# plaque2.net
KiCad netlist of a schematic drawn in EAGLE
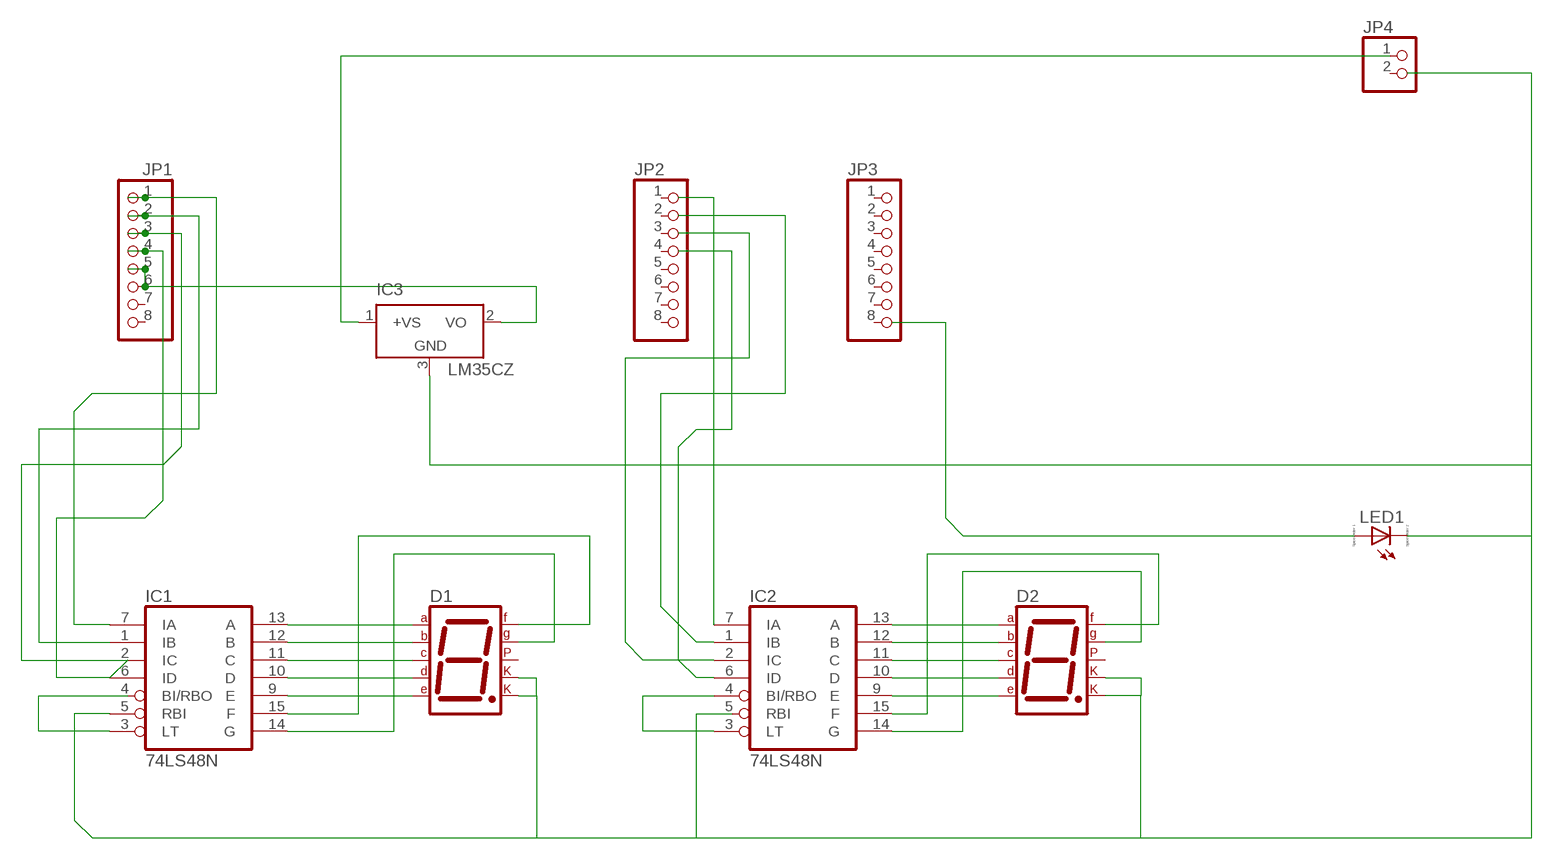
[diagram p0: schematic, sheet 1]

(export (version "E")
  (design (tool "Eeschema 10.0.6"))
  (components
    (comp (ref "D1")
      (value "7SEG-CK")
      (footprint "eagle-import:7SEG-13")
      (libsource (lib "eagle-import") (part "7SEG-CK"))
    )
    (comp (ref "D2")
      (value "7SEG-CK")
      (footprint "eagle-import:7SEG-13")
      (libsource (lib "eagle-import") (part "7SEG-CK"))
    )
    (comp (ref "IC1")
      (value "74LS48N")
      (footprint "eagle-import:DIL16")
      (libsource (lib "eagle-import") (part "7448NLS"))
    )
    (comp (ref "IC2")
      (value "74LS48N")
      (footprint "eagle-import:DIL16")
      (libsource (lib "eagle-import") (part "7448NLS"))
    )
    (comp (ref "IC3")
      (value "LM35CZ")
      (footprint "eagle-import:TO92")
      (libsource (lib "eagle-import") (part "LM35CZ"))
    )
    (comp (ref "JP1")
      (value "PINHD-1X8")
      (footprint "eagle-import:1X08")
      (libsource (lib "eagle-import") (part "PINHD-1X8"))
    )
    (comp (ref "JP2")
      (value "PINHD-1X8")
      (footprint "eagle-import:1X08")
      (libsource (lib "eagle-import") (part "PINHD-1X8"))
    )
    (comp (ref "JP3")
      (value "PINHD-1X8")
      (footprint "eagle-import:1X08")
      (libsource (lib "eagle-import") (part "PINHD-1X8"))
    )
    (comp (ref "JP4")
      (value "PINHD-1X2")
      (footprint "eagle-import:1X02")
      (libsource (lib "eagle-import") (part "PINHD-1X2"))
    )
    (comp (ref "LED1")
      (value "LED_E")
      (footprint "eagle-import:LED_1206")
      (libsource (lib "eagle-import") (part "LED_E"))
    )
  )
  (nets
    (net (code "1") (name "Net-(D1-A)") (class "Default")
      (node (ref "D1") (pin "7") (pinfunction "A_7") (pintype "passive"))
      (node (ref "IC1") (pin "13") (pinfunction "A_13") (pintype "output"))
    )
    (net (code "2") (name "Net-(D1-B)") (class "Default")
      (node (ref "D1") (pin "6") (pinfunction "B_6") (pintype "passive"))
      (node (ref "IC1") (pin "12") (pinfunction "B_12") (pintype "output"))
    )
    (net (code "3") (name "Net-(D1-C)") (class "Default")
      (node (ref "D1") (pin "4") (pinfunction "C_4") (pintype "passive"))
      (node (ref "IC1") (pin "11") (pinfunction "C_11") (pintype "output"))
    )
    (net (code "4") (name "Net-(D1-CK1)") (class "Default")
      (node (ref "D1") (pin "3") (pinfunction "CK1_3") (pintype "passive"))
      (node (ref "D1") (pin "8") (pinfunction "CK2_8") (pintype "passive"))
      (node (ref "D2") (pin "3") (pinfunction "CK1_3") (pintype "passive"))
      (node (ref "D2") (pin "8") (pinfunction "CK2_8") (pintype "passive"))
      (node (ref "IC1") (pin "5") (pinfunction "RBI_5") (pintype "input"))
      (node (ref "IC3") (pin "3") (pinfunction "GND_3") (pintype "power_in"))
      (node (ref "LED1") (pin "C") (pinfunction "C_C") (pintype "passive"))
    )
    (net (code "5") (name "Net-(D1-D)") (class "Default")
      (node (ref "D1") (pin "2") (pinfunction "D_2") (pintype "passive"))
      (node (ref "IC1") (pin "10") (pinfunction "D_10") (pintype "output"))
    )
    (net (code "6") (name "Net-(D1-E)") (class "Default")
      (node (ref "D1") (pin "1") (pinfunction "E_1") (pintype "passive"))
      (node (ref "IC1") (pin "9") (pinfunction "E_9") (pintype "output"))
    )
    (net (code "7") (name "Net-(D1-F)") (class "Default")
      (node (ref "D1") (pin "9") (pinfunction "F_9") (pintype "passive"))
      (node (ref "IC1") (pin "15") (pinfunction "F_15") (pintype "output"))
    )
    (net (code "8") (name "Net-(D1-G)") (class "Default")
      (node (ref "D1") (pin "10") (pinfunction "G_10") (pintype "passive"))
      (node (ref "IC1") (pin "14") (pinfunction "G_14") (pintype "output"))
    )
    (net (code "9") (name "Net-(D2-A)") (class "Default")
      (node (ref "D2") (pin "7") (pinfunction "A_7") (pintype "passive"))
      (node (ref "IC2") (pin "13") (pinfunction "A_13") (pintype "output"))
    )
    (net (code "10") (name "Net-(D2-B)") (class "Default")
      (node (ref "D2") (pin "6") (pinfunction "B_6") (pintype "passive"))
      (node (ref "IC2") (pin "12") (pinfunction "B_12") (pintype "output"))
    )
    (net (code "11") (name "Net-(D2-C)") (class "Default")
      (node (ref "D2") (pin "4") (pinfunction "C_4") (pintype "passive"))
      (node (ref "IC2") (pin "11") (pinfunction "C_11") (pintype "output"))
    )
    (net (code "12") (name "Net-(D2-D)") (class "Default")
      (node (ref "D2") (pin "2") (pinfunction "D_2") (pintype "passive"))
      (node (ref "IC2") (pin "10") (pinfunction "D_10") (pintype "output"))
    )
    (net (code "13") (name "Net-(D2-E)") (class "Default")
      (node (ref "D2") (pin "1") (pinfunction "E_1") (pintype "passive"))
      (node (ref "IC2") (pin "9") (pinfunction "E_9") (pintype "output"))
    )
    (net (code "14") (name "Net-(D2-F)") (class "Default")
      (node (ref "D2") (pin "9") (pinfunction "F_9") (pintype "passive"))
      (node (ref "IC2") (pin "15") (pinfunction "F_15") (pintype "output"))
    )
    (net (code "15") (name "Net-(D2-G)") (class "Default")
      (node (ref "D2") (pin "10") (pinfunction "G_10") (pintype "passive"))
      (node (ref "IC2") (pin "14") (pinfunction "G_14") (pintype "output"))
    )
    (net (code "16") (name "Net-(IC1A-BI{slash}RBO)") (class "Default")
      (node (ref "IC1") (pin "3") (pinfunction "LT_3") (pintype "input"))
      (node (ref "IC1") (pin "4") (pinfunction "BI/RBO_4") (pintype "input"))
    )
    (net (code "17") (name "Net-(IC1A-IA)") (class "Default")
      (node (ref "IC1") (pin "7") (pinfunction "IA_7") (pintype "input"))
      (node (ref "JP1") (pin "1") (pinfunction "1_1") (pintype "passive"))
    )
    (net (code "18") (name "Net-(IC1A-IB)") (class "Default")
      (node (ref "IC1") (pin "1") (pinfunction "IB_1") (pintype "input"))
      (node (ref "JP1") (pin "2") (pinfunction "2_2") (pintype "passive"))
    )
    (net (code "19") (name "Net-(IC1A-ID)") (class "Default")
      (node (ref "IC1") (pin "6") (pinfunction "ID_6") (pintype "input"))
      (node (ref "JP1") (pin "3") (pinfunction "3_3") (pintype "passive"))
      (node (ref "JP1") (pin "4") (pinfunction "4_4") (pintype "passive"))
    )
    (net (code "20") (name "Net-(IC2A-BI{slash}RBO)") (class "Default")
      (node (ref "IC2") (pin "3") (pinfunction "LT_3") (pintype "input"))
      (node (ref "IC2") (pin "4") (pinfunction "BI/RBO_4") (pintype "input"))
    )
    (net (code "21") (name "Net-(IC3-+VS)") (class "Default")
      (node (ref "IC3") (pin "1") (pinfunction "+VS_1") (pintype "input"))
      (node (ref "JP4") (pin "1") (pinfunction "1_1") (pintype "passive"))
    )
    (net (code "22") (name "Net-(IC3-VO)") (class "Default")
      (node (ref "IC3") (pin "2") (pinfunction "VO_2") (pintype "input"))
      (node (ref "JP1") (pin "5") (pinfunction "5_5") (pintype "passive"))
      (node (ref "JP1") (pin "6") (pinfunction "6_6") (pintype "passive"))
    )
    (net (code "23") (name "unconnected-(D1-DP-Pad5)") (class "Default")
      (node (ref "D1") (pin "5") (pinfunction "DP_5") (pintype "passive"))
    )
    (net (code "24") (name "unconnected-(D2-DP-Pad5)") (class "Default")
      (node (ref "D2") (pin "5") (pinfunction "DP_5") (pintype "passive"))
    )
    (net (code "25") (name "unconnected-(IC1A-IC-Pad2)") (class "Default")
      (node (ref "IC1") (pin "2") (pinfunction "IC_2") (pintype "input"))
    )
    (net (code "26") (name "unconnected-(IC2A-IA-Pad7)") (class "Default")
      (node (ref "IC2") (pin "7") (pinfunction "IA_7") (pintype "input"))
    )
    (net (code "27") (name "unconnected-(IC2A-IB-Pad1)") (class "Default")
      (node (ref "IC2") (pin "1") (pinfunction "IB_1") (pintype "input"))
    )
    (net (code "28") (name "unconnected-(IC2A-IC-Pad2)") (class "Default")
      (node (ref "IC2") (pin "2") (pinfunction "IC_2") (pintype "input"))
    )
    (net (code "29") (name "unconnected-(IC2A-ID-Pad6)") (class "Default")
      (node (ref "IC2") (pin "6") (pinfunction "ID_6") (pintype "input"))
    )
    (net (code "30") (name "unconnected-(IC2A-RBI-Pad5)") (class "Default")
      (node (ref "IC2") (pin "5") (pinfunction "RBI_5") (pintype "input"))
    )
    (net (code "31") (name "unconnected-(JP1-Pad7)") (class "Default")
      (node (ref "JP1") (pin "7") (pinfunction "7_7") (pintype "passive"))
    )
    (net (code "32") (name "unconnected-(JP1-Pad8)") (class "Default")
      (node (ref "JP1") (pin "8") (pinfunction "8_8") (pintype "passive"))
    )
    (net (code "33") (name "unconnected-(JP2-Pad1)") (class "Default")
      (node (ref "JP2") (pin "1") (pinfunction "1_1") (pintype "passive"))
    )
    (net (code "34") (name "unconnected-(JP2-Pad2)") (class "Default")
      (node (ref "JP2") (pin "2") (pinfunction "2_2") (pintype "passive"))
    )
    (net (code "35") (name "unconnected-(JP2-Pad3)") (class "Default")
      (node (ref "JP2") (pin "3") (pinfunction "3_3") (pintype "passive"))
    )
    (net (code "36") (name "unconnected-(JP2-Pad4)") (class "Default")
      (node (ref "JP2") (pin "4") (pinfunction "4_4") (pintype "passive"))
    )
    (net (code "37") (name "unconnected-(JP2-Pad5)") (class "Default")
      (node (ref "JP2") (pin "5") (pinfunction "5_5") (pintype "passive"))
    )
    (net (code "38") (name "unconnected-(JP2-Pad6)") (class "Default")
      (node (ref "JP2") (pin "6") (pinfunction "6_6") (pintype "passive"))
    )
    (net (code "39") (name "unconnected-(JP2-Pad7)") (class "Default")
      (node (ref "JP2") (pin "7") (pinfunction "7_7") (pintype "passive"))
    )
    (net (code "40") (name "unconnected-(JP2-Pad8)") (class "Default")
      (node (ref "JP2") (pin "8") (pinfunction "8_8") (pintype "passive"))
    )
    (net (code "41") (name "unconnected-(JP3-Pad1)") (class "Default")
      (node (ref "JP3") (pin "1") (pinfunction "1_1") (pintype "passive"))
    )
    (net (code "42") (name "unconnected-(JP3-Pad2)") (class "Default")
      (node (ref "JP3") (pin "2") (pinfunction "2_2") (pintype "passive"))
    )
    (net (code "43") (name "unconnected-(JP3-Pad3)") (class "Default")
      (node (ref "JP3") (pin "3") (pinfunction "3_3") (pintype "passive"))
    )
    (net (code "44") (name "unconnected-(JP3-Pad4)") (class "Default")
      (node (ref "JP3") (pin "4") (pinfunction "4_4") (pintype "passive"))
    )
    (net (code "45") (name "unconnected-(JP3-Pad5)") (class "Default")
      (node (ref "JP3") (pin "5") (pinfunction "5_5") (pintype "passive"))
    )
    (net (code "46") (name "unconnected-(JP3-Pad6)") (class "Default")
      (node (ref "JP3") (pin "6") (pinfunction "6_6") (pintype "passive"))
    )
    (net (code "47") (name "unconnected-(JP3-Pad7)") (class "Default")
      (node (ref "JP3") (pin "7") (pinfunction "7_7") (pintype "passive"))
    )
    (net (code "48") (name "unconnected-(JP3-Pad8)") (class "Default")
      (node (ref "JP3") (pin "8") (pinfunction "8_8") (pintype "passive"))
    )
    (net (code "49") (name "unconnected-(JP4-Pad2)") (class "Default")
      (node (ref "JP4") (pin "2") (pinfunction "2_2") (pintype "passive"))
    )
    (net (code "50") (name "unconnected-(LED1-PadA)") (class "Default")
      (node (ref "LED1") (pin "A") (pinfunction "A_A") (pintype "passive"))
    )
  )
)
